# QUTMS-TSAL-NEW-S04.net
KiCad netlist of a schematic drawn in Altium Designer
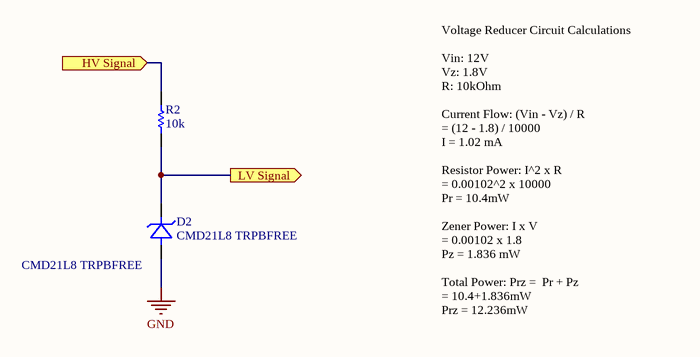
[diagram p0: QUTMS-TSAL-NEW-S04.SchDoc]

(export (version "E")
  (design (tool "Eeschema 10.0.6"))
  (components
    (comp (ref "D2")
      (value "CMD21L8 TRPBFREE")
      (footprint "SODFL160X80-2N")
      (libsource (lib "QUTMS_DiodeLibrary") (part "CMD21L8 TRPBFREE"))
    )
    (comp (ref "R2")
      (value "10k")
      (footprint "Res_ThinFilm_0603")
      (description "Resistor, SMD, 10k, 0.1W, 5%, 0603")
      (libsource (lib "StandardResistors") (part "10k 5% 0603"))
    )
  )
  (nets
    (net (code "1") (name "/HV Signal") (class "Default")
      (node (ref "R2") (pin "2") (pinfunction "2_2") (pintype "passive"))
    )
    (net (code "2") (name "/LV Signal") (class "Default")
      (node (ref "D2") (pin "K") (pinfunction "Cathode_K") (pintype "passive"))
      (node (ref "R2") (pin "1") (pinfunction "1_1") (pintype "passive"))
    )
    (net (code "3") (name "GND") (class "Default")
      (node (ref "D2") (pin "A") (pinfunction "Anode_A") (pintype "passive"))
    )
  )
)
